# MiniBot1.net
KiCad netlist of a schematic drawn in EAGLE
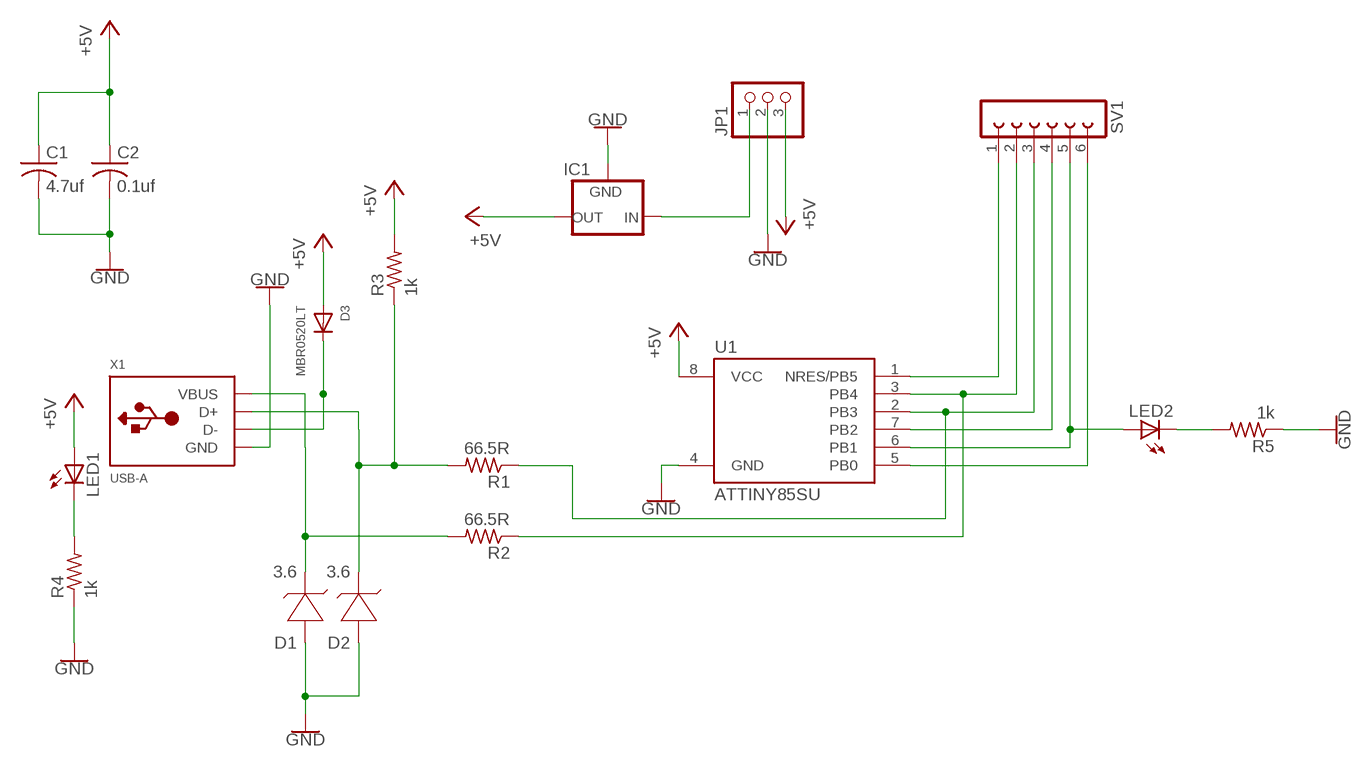
[diagram p0: schematic, sheet 1]

(export (version "E")
  (design (tool "Eeschema 10.0.6"))
  (components
    (comp (ref "C1")
      (value "4.7uf")
      (footprint "eagle-import:C0402")
      (libsource (lib "eagle-import") (part "C-USC0402"))
    )
    (comp (ref "C2")
      (value "0.1uf")
      (footprint "eagle-import:C0402")
      (libsource (lib "eagle-import") (part "C-USC0402"))
    )
    (comp (ref "D1")
      (value "3.6")
      (footprint "eagle-import:SOD123")
      (libsource (lib "eagle-import") (part "ZENER"))
    )
    (comp (ref "D2")
      (value "3.6")
      (footprint "eagle-import:SOD123")
      (libsource (lib "eagle-import") (part "ZENER"))
    )
    (comp (ref "D3")
      (value "MBR0520LT")
      (footprint "eagle-import:SOD-523")
      (libsource (lib "eagle-import") (part "DIODESOD-523"))
    )
    (comp (ref "IC1")
      (value "MCP1700INLINE")
      (footprint "eagle-import:TO92-INLINE")
      (libsource (lib "eagle-import") (part "MCP1700INLINE"))
    )
    (comp (ref "JP1")
      (value "PINHD-1X3")
      (footprint "eagle-import:1X03")
      (libsource (lib "eagle-import") (part "PINHD-1X3"))
    )
    (comp (ref "LED1")
      (value "LED")
      (footprint "eagle-import:SMARTLED-TTW")
      (libsource (lib "eagle-import") (part "LED"))
    )
    (comp (ref "LED2")
      (value "LED")
      (footprint "eagle-import:SMARTLED-TTW")
      (libsource (lib "eagle-import") (part "LED"))
    )
    (comp (ref "R1")
      (value "66.5R")
      (footprint "eagle-import:M0805")
      (libsource (lib "eagle-import") (part "R-US_M0805"))
    )
    (comp (ref "R2")
      (value "66.5R")
      (footprint "eagle-import:M0805")
      (libsource (lib "eagle-import") (part "R-US_M0805"))
    )
    (comp (ref "R3")
      (value "1k")
      (footprint "eagle-import:M0805")
      (libsource (lib "eagle-import") (part "R-US_M0805"))
    )
    (comp (ref "R4")
      (value "1k")
      (footprint "eagle-import:M0805")
      (libsource (lib "eagle-import") (part "R-US_M0805"))
    )
    (comp (ref "R5")
      (value "1k")
      (footprint "eagle-import:M0805")
      (libsource (lib "eagle-import") (part "R-US_M0805"))
    )
    (comp (ref "SV1")
      (value "FE06-1")
      (footprint "eagle-import:FE06")
      (libsource (lib "eagle-import") (part "FE06-1"))
    )
    (comp (ref "U1")
      (value "ATTINY85SU")
      (footprint "eagle-import:ATTINY85")
      (libsource (lib "eagle-import") (part "ATTINY85SU"))
    )
    (comp (ref "X1")
      (value "USB-A")
      (footprint "eagle-import:MOLEX_480371000")
      (libsource (lib "eagle-import") (part "USB-A"))
    )
  )
  (nets
    (net (code "1") (name "+5V") (class "Default")
      (node (ref "C1") (pin "1") (pinfunction "1_1") (pintype "passive"))
      (node (ref "C2") (pin "1") (pinfunction "1_1") (pintype "passive"))
      (node (ref "D3") (pin "A") (pinfunction "A_A") (pintype "passive"))
      (node (ref "IC1") (pin "3") (pinfunction "OUT_3") (pintype "passive"))
      (node (ref "JP1") (pin "3") (pinfunction "3_3") (pintype "passive"))
      (node (ref "LED1") (pin "A@1") (pinfunction "A_A@1") (pintype "passive"))
      (node (ref "R3") (pin "2") (pinfunction "2_2") (pintype "passive"))
      (node (ref "U1") (pin "8") (pinfunction "VCC_8") (pintype "power_in"))
    )
    (net (code "2") (name "GND") (class "Default")
      (node (ref "C1") (pin "2") (pinfunction "2_2") (pintype "passive"))
      (node (ref "C2") (pin "2") (pinfunction "2_2") (pintype "passive"))
      (node (ref "D1") (pin "A") (pinfunction "+_A") (pintype "passive"))
      (node (ref "D2") (pin "A") (pinfunction "+_A") (pintype "passive"))
      (node (ref "IC1") (pin "1") (pinfunction "GND_1") (pintype "input"))
      (node (ref "JP1") (pin "2") (pinfunction "2_2") (pintype "passive"))
      (node (ref "R4") (pin "1") (pinfunction "1_1") (pintype "passive"))
      (node (ref "R5") (pin "1") (pinfunction "1_1") (pintype "passive"))
      (node (ref "U1") (pin "4") (pinfunction "GND_4") (pintype "power_in"))
      (node (ref "X1") (pin "4") (pinfunction "GND_4") (pintype "power_in"))
    )
    (net (code "3") (name "Net-(D1--)") (class "Default")
      (node (ref "D1") (pin "C") (pinfunction "-_C") (pintype "passive"))
      (node (ref "R2") (pin "2") (pinfunction "2_2") (pintype "passive"))
      (node (ref "X1") (pin "1") (pinfunction "VBUS_1") (pintype "power_in"))
    )
    (net (code "4") (name "Net-(D2--)") (class "Default")
      (node (ref "D2") (pin "C") (pinfunction "-_C") (pintype "passive"))
      (node (ref "R1") (pin "2") (pinfunction "2_2") (pintype "passive"))
      (node (ref "R3") (pin "1") (pinfunction "1_1") (pintype "passive"))
      (node (ref "X1") (pin "3") (pinfunction "D+_3") (pintype "bidirectional"))
    )
    (net (code "5") (name "Net-(D3-C)") (class "Default")
      (node (ref "D3") (pin "K") (pinfunction "C_K") (pintype "passive"))
      (node (ref "X1") (pin "2") (pinfunction "D-_2") (pintype "bidirectional"))
    )
    (net (code "6") (name "Net-(IC1-IN)") (class "Default")
      (node (ref "IC1") (pin "2") (pinfunction "IN_2") (pintype "input"))
      (node (ref "JP1") (pin "1") (pinfunction "1_1") (pintype "passive"))
    )
    (net (code "7") (name "Net-(LED1-C)") (class "Default")
      (node (ref "LED1") (pin "C@1") (pinfunction "C_C@1") (pintype "passive"))
      (node (ref "R4") (pin "2") (pinfunction "2_2") (pintype "passive"))
    )
    (net (code "8") (name "Net-(LED2-A)") (class "Default")
      (node (ref "LED2") (pin "A@1") (pinfunction "A_A@1") (pintype "passive"))
      (node (ref "SV1") (pin "5") (pinfunction "5_5") (pintype "passive"))
      (node (ref "U1") (pin "6") (pinfunction "PB1_6") (pintype "bidirectional"))
    )
    (net (code "9") (name "Net-(LED2-C)") (class "Default")
      (node (ref "LED2") (pin "C@1") (pinfunction "C_C@1") (pintype "passive"))
      (node (ref "R5") (pin "2") (pinfunction "2_2") (pintype "passive"))
    )
    (net (code "10") (name "Net-(U1-NRES{slash}PB5)") (class "Default")
      (node (ref "SV1") (pin "1") (pinfunction "1_1") (pintype "passive"))
      (node (ref "U1") (pin "1") (pinfunction "NRES/PB5_1") (pintype "bidirectional"))
    )
    (net (code "11") (name "Net-(U1-PB0)") (class "Default")
      (node (ref "SV1") (pin "6") (pinfunction "6_6") (pintype "passive"))
      (node (ref "U1") (pin "5") (pinfunction "PB0_5") (pintype "bidirectional"))
    )
    (net (code "12") (name "Net-(U1-PB2)") (class "Default")
      (node (ref "SV1") (pin "4") (pinfunction "4_4") (pintype "passive"))
      (node (ref "U1") (pin "7") (pinfunction "PB2_7") (pintype "bidirectional"))
    )
    (net (code "13") (name "Net-(U1-PB3)") (class "Default")
      (node (ref "R1") (pin "1") (pinfunction "1_1") (pintype "passive"))
      (node (ref "SV1") (pin "3") (pinfunction "3_3") (pintype "passive"))
      (node (ref "U1") (pin "2") (pinfunction "PB3_2") (pintype "bidirectional"))
    )
    (net (code "14") (name "Net-(U1-PB4)") (class "Default")
      (node (ref "R2") (pin "1") (pinfunction "1_1") (pintype "passive"))
      (node (ref "SV1") (pin "2") (pinfunction "2_2") (pintype "passive"))
      (node (ref "U1") (pin "3") (pinfunction "PB4_3") (pintype "bidirectional"))
    )
  )
)
